# TIDA-010967_Decoupling_caps.net
KiCad netlist of a schematic drawn in Altium Designer
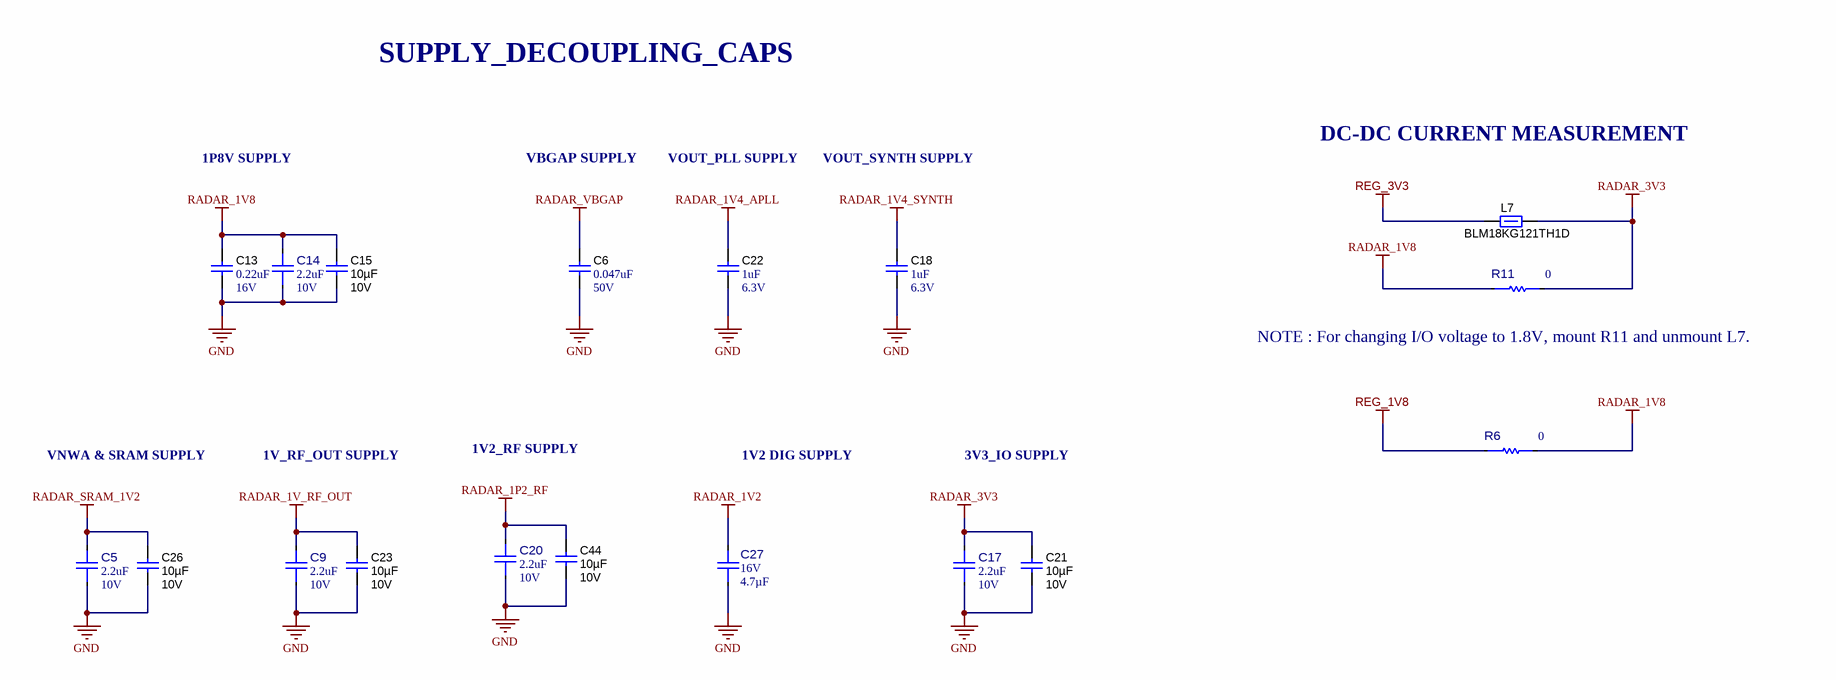
[diagram p0: TIDA-010967_Decoupling_caps.SchDoc]

(export (version "E")
  (design (tool "Eeschema 10.0.6"))
  (components
    (comp (ref "C5")
      (value "GRM155R61A225ME01D")
      (footprint "FP-GRM155R61A225ME01D_0402-MFG")
      (description "Chip Multilayer Ceramic Capacitors for General Purpose, 0402, 2.2uF, X5R, 15%, 20%, 10V")
      (fields
        (field (name "VALUEDISPLAYED") "2.2uF")
        (field (name "MANUFACTURER") "Murata")
        (field (name "VDC_V") "10V")
      )
      (libsource (lib "Altium Vault - TI") (part "SYM-GRM155R61A225ME01D"))
    )
    (comp (ref "C6")
      (value "C1005X7R1H473K050BB")
      (footprint "0402L")
      (description "CAP, CERM, 0.047 uF, 50 V, +/- 10%, X7R, 0402")
      (fields
        (field (name "MANUFACTURER") "TDK")
        (field (name "VDC_V") "50V")
        (field (name "VALUEDISPLAYED") "0.047uF")
        (field (name "PUBLISHER") "Texas Instruments")
      )
      (libsource (lib "Altium Vault - TI") (part "Capacitor"))
    )
    (comp (ref "C9")
      (value "GRM155R61A225ME01D")
      (footprint "FP-GRM155R61A225ME01D_0402-MFG")
      (description "Chip Multilayer Ceramic Capacitors for General Purpose, 0402, 2.2uF, X5R, 15%, 20%, 10V")
      (fields
        (field (name "VALUEDISPLAYED") "2.2uF")
        (field (name "MANUFACTURER") "Murata")
        (field (name "VDC_V") "10V")
      )
      (libsource (lib "Altium Vault - TI") (part "SYM-GRM155R61A225ME01D"))
    )
    (comp (ref "C13")
      (value "GRM155R71C224KA12D")
      (footprint "0402L")
      (description "CAP, CERM, 0.22 uF, 16 V, +/- 10%, X7R, 0402")
      (fields
        (field (name "MANUFACTURER") "MuRata")
        (field (name "VDC_V") "16V")
        (field (name "VALUEDISPLAYED") "0.22uF")
        (field (name "PUBLISHER") "Texas Instruments")
      )
      (libsource (lib "Altium Vault - TI") (part "Capacitor"))
    )
    (comp (ref "C14")
      (value "GRM155R61A225ME01D")
      (footprint "FP-GRM155R61A225ME01D_0402-MFG")
      (description "Chip Multilayer Ceramic Capacitors for General Purpose, 0402, 2.2uF, X5R, 15%, 20%, 10V")
      (fields
        (field (name "VALUEDISPLAYED") "2.2uF")
        (field (name "MANUFACTURER") "Murata")
        (field (name "VDC_V") "10V")
      )
      (libsource (lib "Altium Vault - TI") (part "SYM-GRM155R61A225ME01D"))
    )
    (comp (ref "C15")
      (value "GRM188Z71A106MA73D")
      (footprint "0603L")
      (description "CAP, CERM, 10 uF, 10 V, +/- 20%, X7R, 0603")
      (fields
        (field (name "MANUFACTURER") "MuRata")
        (field (name "VALUE2") "10V")
        (field (name "CAP_F") "10µF")
        (field (name "PUBLISHER") "Texas Instruments")
      )
      (libsource (lib "Altium Vault - TI") (part "Capacitor"))
    )
    (comp (ref "C17")
      (value "GRM155R61A225ME01D")
      (footprint "FP-GRM155R61A225ME01D_0402-MFG")
      (description "Chip Multilayer Ceramic Capacitors for General Purpose, 0402, 2.2uF, X5R, 15%, 20%, 10V")
      (fields
        (field (name "VALUEDISPLAYED") "2.2uF")
        (field (name "MANUFACTURER") "Murata")
        (field (name "VDC_V") "10V")
      )
      (libsource (lib "Altium Vault - TI") (part "SYM-GRM155R61A225ME01D"))
    )
    (comp (ref "C18")
      (value "GRM155R70J105KA12D")
      (footprint "0402S")
      (description "CAP, CERM, 1 uF, 6.3 V,+/- 10%, X7R, 0402")
      (fields
        (field (name "MANUFACTURER") "MuRata")
        (field (name "VDC_V") "6.3V")
        (field (name "VALUEDISPLAYED") "1uF")
        (field (name "PUBLISHER") "Texas Instruments")
      )
      (libsource (lib "Altium Vault - TI") (part "Capacitor"))
    )
    (comp (ref "C20")
      (value "GRM155R61A225ME01D")
      (footprint "FP-GRM155R61A225ME01D_0402-MFG")
      (description "Chip Multilayer Ceramic Capacitors for General Purpose, 0402, 2.2uF, X5R, 15%, 20%, 10V")
      (fields
        (field (name "VALUEDISPLAYED") "2.2uF")
        (field (name "MANUFACTURER") "Murata")
        (field (name "VDC_V") "10V")
      )
      (libsource (lib "Altium Vault - TI") (part "SYM-GRM155R61A225ME01D"))
    )
    (comp (ref "C21")
      (value "GRM188Z71A106MA73D")
      (footprint "0603L")
      (description "CAP, CERM, 10 uF, 10 V, +/- 20%, X7R, 0603")
      (fields
        (field (name "MANUFACTURER") "MuRata")
        (field (name "VALUE2") "10V")
        (field (name "CAP_F") "10µF")
        (field (name "PUBLISHER") "Texas Instruments")
      )
      (libsource (lib "Altium Vault - TI") (part "Capacitor"))
    )
    (comp (ref "C22")
      (value "GRM155R70J105KA12D")
      (footprint "0402S")
      (description "CAP, CERM, 1 uF, 6.3 V,+/- 10%, X7R, 0402")
      (fields
        (field (name "MANUFACTURER") "MuRata")
        (field (name "VDC_V") "6.3V")
        (field (name "VALUEDISPLAYED") "1uF")
        (field (name "PUBLISHER") "Texas Instruments")
      )
      (libsource (lib "Altium Vault - TI") (part "Capacitor"))
    )
    (comp (ref "C23")
      (value "GRM188Z71A106MA73D")
      (footprint "0603L")
      (description "CAP, CERM, 10 uF, 10 V, +/- 20%, X7R, 0603")
      (fields
        (field (name "MANUFACTURER") "MuRata")
        (field (name "VALUE2") "10V")
        (field (name "CAP_F") "10µF")
        (field (name "PUBLISHER") "Texas Instruments")
      )
      (libsource (lib "Altium Vault - TI") (part "Capacitor"))
    )
    (comp (ref "C26")
      (value "GRM188Z71A106MA73D")
      (footprint "0603L")
      (description "CAP, CERM, 10 uF, 10 V, +/- 20%, X7R, 0603")
      (fields
        (field (name "MANUFACTURER") "MuRata")
        (field (name "VALUE2") "10V")
        (field (name "CAP_F") "10µF")
        (field (name "PUBLISHER") "Texas Instruments")
      )
      (libsource (lib "Altium Vault - TI") (part "Capacitor"))
    )
    (comp (ref "C27")
      (value "GCJ21BR71C475KA01L")
      (footprint "FP-GCJ21BR71C475KA01L_0805-MFG")
      (description "Multilayer Ceramic Capacitors MLCC - SMD/SMT 0805 4.7uF 10%, 16VDC,  X7R 15%")
      (fields
        (field (name "MANUFACTURER") "Murata")
        (field (name "VDC_V") "16V")
        (field (name "CAP_F") "4.7µF")
      )
      (libsource (lib "Altium Vault - TI") (part "SYM-GCJ21BR71C475KA01L"))
    )
    (comp (ref "C44")
      (value "GRM188Z71A106MA73D")
      (footprint "0603L")
      (description "CAP, CERM, 10 uF, 10 V, +/- 20%, X7R, 0603")
      (fields
        (field (name "MANUFACTURER") "MuRata")
        (field (name "VALUE2") "10V")
        (field (name "CAP_F") "10µF")
        (field (name "PUBLISHER") "Texas Instruments")
      )
      (libsource (lib "Altium Vault - TI") (part "Capacitor"))
    )
    (comp (ref "L7")
      (value "BLM18KG121TH1D")
      (footprint "0603L")
      (description "Ferrite Bead, 120 ohm @ 100 MHz, 1.9 A, 0603")
      (fields (field (name "MANUFACTURER") "MuRata"))
      (libsource (lib "Altium Vault - TI") (part "Ferrite_Bead"))
    )
    (comp (ref "R6")
      (value "ERJ-3GEY0R00V")
      (footprint "FP-ERJ-3GEY0R00V_0603-MFG")
      (description "0 Ohms Jumper 0.1W, 1/10W Chip Resistor 0603 (1608 Metric) Automotive AEC-Q200 Thick Film")
      (fields
        (field (name "MANUFACTURER") "Panasonic")
        (field (name "RES_OHM") "0")
        (field (name "DIGIKEY PART NUMBER") "P0.0GCT-ND")
      )
      (libsource (lib "Altium Vault - TI") (part "SYM-ERJ-3GEY0R00V"))
    )
    (comp (ref "R11")
      (value "ERJ-3GEY0R00V")
      (footprint "FP-ERJ-3GEY0R00V_0603-MFG")
      (description "0 Ohms Jumper 0.1W, 1/10W Chip Resistor 0603 (1608 Metric) Automotive AEC-Q200 Thick Film")
      (fields
        (field (name "MANUFACTURER") "Panasonic")
        (field (name "RES_OHM") "0")
        (field (name "DIGIKEY PART NUMBER") "P0.0GCT-ND")
      )
      (libsource (lib "Altium Vault - TI") (part "SYM-ERJ-3GEY0R00V"))
    )
  )
  (nets
    (net (code "1") (name "GND") (class "Default")
      (node (ref "C13") (pin "2") (pinfunction "2_2") (pintype "passive"))
      (node (ref "C14") (pin "1") (pinfunction "1_1") (pintype "passive"))
      (node (ref "C15") (pin "2") (pinfunction "2_2") (pintype "passive"))
      (node (ref "C17") (pin "1") (pinfunction "1_1") (pintype "passive"))
      (node (ref "C18") (pin "2") (pinfunction "2_2") (pintype "passive"))
      (node (ref "C20") (pin "1") (pinfunction "1_1") (pintype "passive"))
      (node (ref "C21") (pin "2") (pinfunction "2_2") (pintype "passive"))
      (node (ref "C22") (pin "2") (pinfunction "2_2") (pintype "passive"))
      (node (ref "C23") (pin "2") (pinfunction "2_2") (pintype "passive"))
      (node (ref "C26") (pin "2") (pinfunction "2_2") (pintype "passive"))
      (node (ref "C27") (pin "1") (pinfunction "1_1") (pintype "passive"))
      (node (ref "C44") (pin "2") (pinfunction "2_2") (pintype "passive"))
      (node (ref "C5") (pin "1") (pinfunction "1_1") (pintype "passive"))
      (node (ref "C6") (pin "2") (pinfunction "2_2") (pintype "passive"))
      (node (ref "C9") (pin "1") (pinfunction "1_1") (pintype "passive"))
    )
    (net (code "2") (name "RADAR_1P2_RF") (class "Default")
      (node (ref "C20") (pin "2") (pinfunction "2_2") (pintype "passive"))
      (node (ref "C44") (pin "1") (pinfunction "1_1") (pintype "passive"))
    )
    (net (code "3") (name "RADAR_1V2") (class "Default")
      (node (ref "C27") (pin "2") (pinfunction "2_2") (pintype "passive"))
    )
    (net (code "4") (name "RADAR_1V4_APLL") (class "Default")
      (node (ref "C22") (pin "1") (pinfunction "1_1") (pintype "passive"))
    )
    (net (code "5") (name "RADAR_1V4_SYNTH") (class "Default")
      (node (ref "C18") (pin "1") (pinfunction "1_1") (pintype "passive"))
    )
    (net (code "6") (name "RADAR_1V8") (class "Default")
      (node (ref "C13") (pin "1") (pinfunction "1_1") (pintype "passive"))
      (node (ref "C14") (pin "2") (pinfunction "2_2") (pintype "passive"))
      (node (ref "C15") (pin "1") (pinfunction "1_1") (pintype "passive"))
      (node (ref "R11") (pin "1") (pinfunction "1_1") (pintype "passive"))
      (node (ref "R6") (pin "2") (pinfunction "2_2") (pintype "passive"))
    )
    (net (code "7") (name "RADAR_1V_RF_OUT") (class "Default")
      (node (ref "C23") (pin "1") (pinfunction "1_1") (pintype "passive"))
      (node (ref "C9") (pin "2") (pinfunction "2_2") (pintype "passive"))
    )
    (net (code "8") (name "RADAR_3V3") (class "Default")
      (node (ref "C17") (pin "2") (pinfunction "2_2") (pintype "passive"))
      (node (ref "C21") (pin "1") (pinfunction "1_1") (pintype "passive"))
      (node (ref "L7") (pin "2") (pinfunction "2_2") (pintype "passive"))
      (node (ref "R11") (pin "2") (pinfunction "2_2") (pintype "passive"))
    )
    (net (code "9") (name "RADAR_SRAM_1V2") (class "Default")
      (node (ref "C26") (pin "1") (pinfunction "1_1") (pintype "passive"))
      (node (ref "C5") (pin "2") (pinfunction "2_2") (pintype "passive"))
    )
    (net (code "10") (name "RADAR_VBGAP") (class "Default")
      (node (ref "C6") (pin "1") (pinfunction "1_1") (pintype "passive"))
    )
    (net (code "11") (name "REG_1V8") (class "Default")
      (node (ref "R6") (pin "1") (pinfunction "1_1") (pintype "passive"))
    )
    (net (code "12") (name "REG_3V3") (class "Default")
      (node (ref "L7") (pin "1") (pinfunction "1_1") (pintype "passive"))
    )
  )
)
